# IMU.net
KiCad netlist of a schematic drawn in Altium Designer
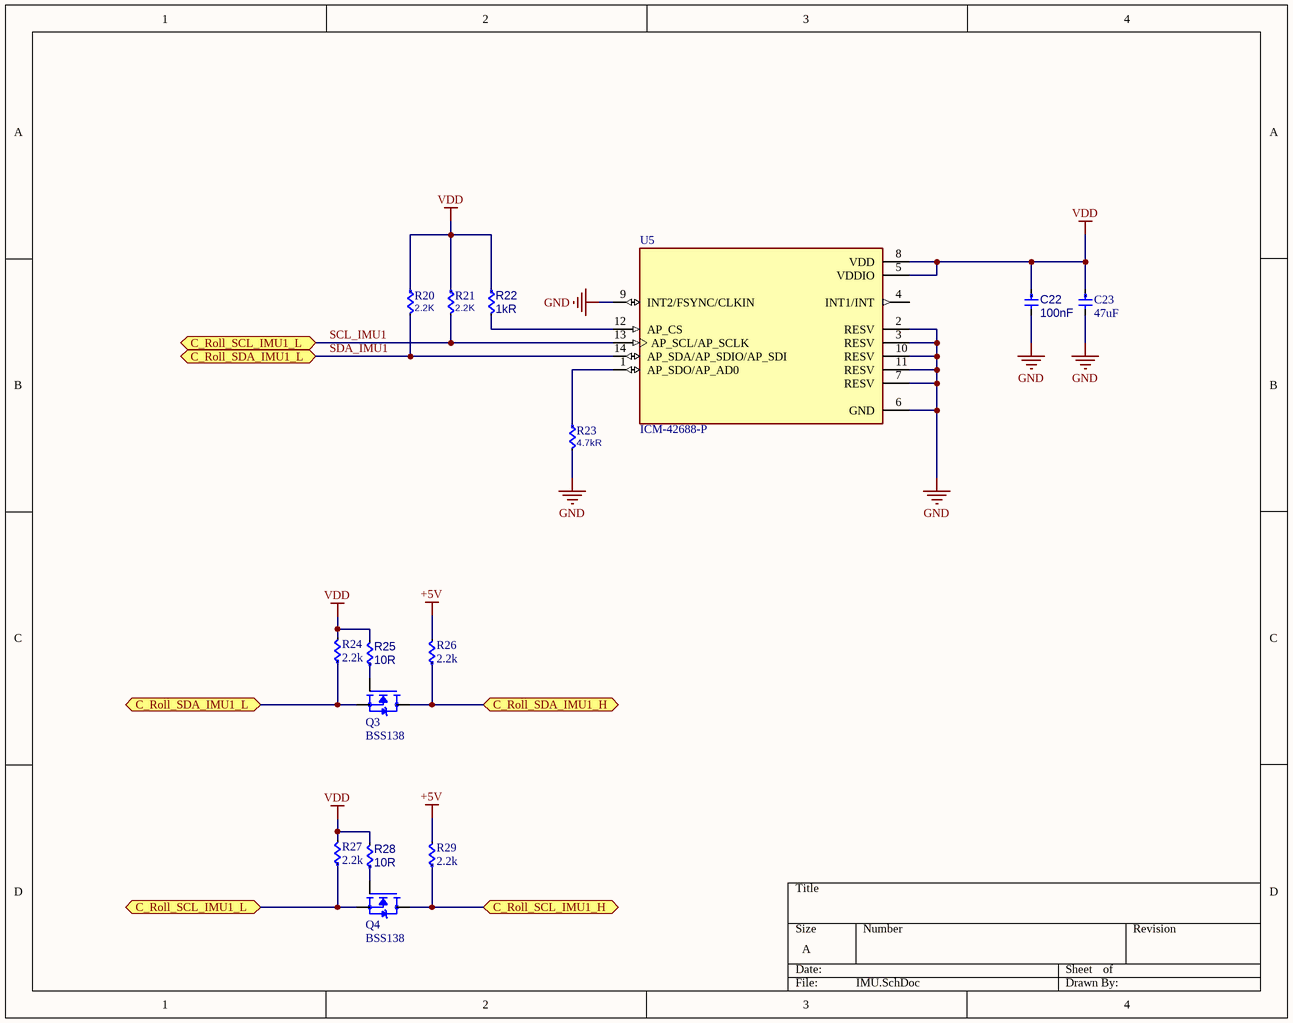
[diagram p0: IMU.SchDoc]

(export (version "E")
  (design (tool "Eeschema 10.0.6"))
  (components
    (comp (ref "C22")
      (value "C0603C104M5RACTU")
      (footprint "CAP0603")
      (description "CAP CER 0.1UF 50V X7R 0603")
      (fields (field (name "TOLERANCE") "20%") (field (name "CAPACITANCE") "100nF"))
      (libsource (lib "rtr") (part "CMP-00691-1"))
    )
    (comp (ref "C23")
      (value "CL21A476MQYNNNE")
      (footprint "CAP0805")
      (description "CAP CER 47UF 6.3V X5R 0805")
      (fields (field (name "TOLERANCE") "20%") (field (name "CAPACITANCE") "47uF"))
      (libsource (lib "rtr") (part "885012107014"))
    )
    (comp (ref "Q3")
      (value "BSS138")
      (footprint "BSS138")
      (description "N-Channel 50 V 220mA (Ta) 350mW (Ta) Surface Mount SOT-23-3")
      (fields (field (name "MF") "onsemi"))
      (libsource (lib "Sbus to Uart") (part "BSS138"))
    )
    (comp (ref "Q4")
      (value "BSS138")
      (footprint "BSS138")
      (description "N-Channel 50 V 220mA (Ta) 350mW (Ta) Surface Mount SOT-23-3")
      (fields (field (name "MF") "onsemi"))
      (libsource (lib "Sbus to Uart") (part "BSS138"))
    )
    (comp (ref "R20")
      (value "RC0603FR-072K2L")
      (footprint "RES0603")
      (description "RES SMD 2.2K OHM 1% 1/10W 0603")
      (fields (field (name "TOLERANCE") "5%") (field (name "RESISTANCE") "2.2K"))
      (libsource (lib "rtr") (part "CMP-01404-1"))
    )
    (comp (ref "R21")
      (value "RC0603FR-072K2L")
      (footprint "RES0603")
      (description "RES SMD 2.2K OHM 1% 1/10W 0603")
      (fields (field (name "TOLERANCE") "5%") (field (name "RESISTANCE") "2.2K"))
      (libsource (lib "rtr") (part "CMP-01404-1"))
    )
    (comp (ref "R22")
      (value "RC0603FR-071KL")
      (footprint "RES0603")
      (description "RES SMD 1K OHM 1% 1/10W 0603")
      (fields
        (field (name "MANUFACTURER") "Yageo")
        (field (name "TOLERANCE") "1%")
        (field (name "RESISTANCE") "1kR")
      )
      (libsource (lib "rtr") (part "CMP-00067-1"))
    )
    (comp (ref "R23")
      (value "RC0603JR-074K7L")
      (footprint "RES0603")
      (description "RES SMD 4.7K OHM 5% 1/10W 0603")
      (fields (field (name "TOLERANCE") "5%") (field (name "RESISTANCE") "4.7kR"))
      (libsource (lib "rtr") (part "CMP-01404-1"))
    )
    (comp (ref "R24")
      (value "2.2k")
      (footprint "RES0603")
      (description "Res Thick Film 0603 2.2K Ohm 1% 0.1W(1/10W) +/-100ppm/C Epoxy Pad SMD T/R")
      (fields
        (field (name "MANUFACTURER") "Yageo Group")
        (field (name "MANUFACTURER PART NUMBER") "RC0603FR-072K2L")
      )
      (libsource (lib "Yaw-Ofil") (part "RC0603FR-072K2L"))
    )
    (comp (ref "R25")
      (value "MCR03EZPJ100")
      (footprint "RES0603")
      (description "RES SMD 10 OHM 5% 1/10W 0603")
      (fields (field (name "TOLERANCE") "5%") (field (name "RESISTANCE") "10R"))
      (libsource (lib "JetsonNX_CSI") (part "CMP-01078-4"))
    )
    (comp (ref "R26")
      (value "2.2k")
      (footprint "RES0603")
      (description "Res Thick Film 0603 2.2K Ohm 1% 0.1W(1/10W) +/-100ppm/C Epoxy Pad SMD T/R")
      (fields
        (field (name "MANUFACTURER") "Yageo Group")
        (field (name "MANUFACTURER PART NUMBER") "RC0603FR-072K2L")
      )
      (libsource (lib "Yaw-Ofil") (part "RC0603FR-072K2L"))
    )
    (comp (ref "R27")
      (value "2.2k")
      (footprint "RES0603")
      (description "Res Thick Film 0603 2.2K Ohm 1% 0.1W(1/10W) +/-100ppm/C Epoxy Pad SMD T/R")
      (fields
        (field (name "MANUFACTURER") "Yageo Group")
        (field (name "MANUFACTURER PART NUMBER") "RC0603FR-072K2L")
      )
      (libsource (lib "Yaw-Ofil") (part "RC0603FR-072K2L"))
    )
    (comp (ref "R28")
      (value "MCR03EZPJ100")
      (footprint "RES0603")
      (description "RES SMD 10 OHM 5% 1/10W 0603")
      (fields (field (name "TOLERANCE") "5%") (field (name "RESISTANCE") "10R"))
      (libsource (lib "JetsonNX_CSI") (part "CMP-01078-4"))
    )
    (comp (ref "R29")
      (value "2.2k")
      (footprint "RES0603")
      (description "Res Thick Film 0603 2.2K Ohm 1% 0.1W(1/10W) +/-100ppm/C Epoxy Pad SMD T/R")
      (fields
        (field (name "MANUFACTURER") "Yageo Group")
        (field (name "MANUFACTURER PART NUMBER") "RC0603FR-072K2L")
      )
      (libsource (lib "Yaw-Ofil") (part "RC0603FR-072K2L"))
    )
    (comp (ref "U5")
      (value "ICM-42688-P")
      (footprint "ICM-42688-P")
      (description "Accelerometer, Gyroscope, 6 Axis Sensor Output")
      (libsource (lib "RTR") (part "ICM-42688-P"))
    )
  )
  (nets
    (net (code "1") (name "+5V") (class "Default")
      (node (ref "R26") (pin "2") (pinfunction "2_2") (pintype "passive"))
      (node (ref "R29") (pin "2") (pinfunction "2_2") (pintype "passive"))
    )
    (net (code "2") (name "/C_Roll_SCL_IMU1_H") (class "Default")
      (node (ref "Q4") (pin "3") (pinfunction "D_3") (pintype "passive"))
      (node (ref "R29") (pin "1") (pinfunction "1_1") (pintype "passive"))
    )
    (net (code "3") (name "/C_Roll_SDA_IMU1_H") (class "Default")
      (node (ref "Q3") (pin "3") (pinfunction "D_3") (pintype "passive"))
      (node (ref "R26") (pin "1") (pinfunction "1_1") (pintype "passive"))
    )
    (net (code "4") (name "/SCL_IMU1") (class "Default")
      (node (ref "Q4") (pin "2") (pinfunction "S_2") (pintype "passive"))
      (node (ref "R21") (pin "2") (pinfunction "2_2") (pintype "passive"))
      (node (ref "R27") (pin "1") (pinfunction "1_1") (pintype "passive"))
      (node (ref "U5") (pin "13") (pinfunction "AP_SCL/AP_SCLK_13") (pintype "input"))
    )
    (net (code "5") (name "/SDA_IMU1") (class "Default")
      (node (ref "Q3") (pin "2") (pinfunction "S_2") (pintype "passive"))
      (node (ref "R20") (pin "2") (pinfunction "2_2") (pintype "passive"))
      (node (ref "R24") (pin "1") (pinfunction "1_1") (pintype "passive"))
      (node (ref "U5") (pin "14") (pinfunction "AP_SDA/AP_SDIO/AP_SDI_14") (pintype "bidirectional"))
    )
    (net (code "6") (name "GND") (class "Default")
      (node (ref "C22") (pin "2") (pinfunction "2_2") (pintype "passive"))
      (node (ref "C23") (pin "2") (pinfunction "2_2") (pintype "passive"))
      (node (ref "R23") (pin "2") (pinfunction "2_2") (pintype "passive"))
      (node (ref "U5") (pin "10") (pinfunction "RESV_10") (pintype "passive"))
      (node (ref "U5") (pin "11") (pinfunction "RESV_11") (pintype "passive"))
      (node (ref "U5") (pin "2") (pinfunction "RESV_2") (pintype "passive"))
      (node (ref "U5") (pin "3") (pinfunction "RESV_3") (pintype "passive"))
      (node (ref "U5") (pin "6") (pinfunction "GND_6") (pintype "power_in"))
      (node (ref "U5") (pin "7") (pinfunction "RESV_7") (pintype "passive"))
      (node (ref "U5") (pin "9") (pinfunction "INT2/FSYNC/CLKIN_9") (pintype "bidirectional"))
    )
    (net (code "7") (name "Net-(Q3-G)") (class "Default")
      (node (ref "Q3") (pin "1") (pinfunction "G_1") (pintype "passive"))
      (node (ref "R25") (pin "1") (pinfunction "1_1") (pintype "passive"))
    )
    (net (code "8") (name "Net-(Q4-G)") (class "Default")
      (node (ref "Q4") (pin "1") (pinfunction "G_1") (pintype "passive"))
      (node (ref "R28") (pin "1") (pinfunction "1_1") (pintype "passive"))
    )
    (net (code "9") (name "Net-(U5-AP_CS)") (class "Default")
      (node (ref "R22") (pin "2") (pinfunction "2_2") (pintype "passive"))
      (node (ref "U5") (pin "12") (pinfunction "AP_CS_12") (pintype "input"))
    )
    (net (code "10") (name "Net-(U5-AP_SDO{slash}AP_AD0)") (class "Default")
      (node (ref "R23") (pin "1") (pinfunction "1_1") (pintype "passive"))
      (node (ref "U5") (pin "1") (pinfunction "AP_SDO/AP_AD0_1") (pintype "bidirectional"))
    )
    (net (code "11") (name "VDD") (class "Default")
      (node (ref "C22") (pin "1") (pinfunction "1_1") (pintype "passive"))
      (node (ref "C23") (pin "1") (pinfunction "1_1") (pintype "passive"))
      (node (ref "R20") (pin "1") (pinfunction "1_1") (pintype "passive"))
      (node (ref "R21") (pin "1") (pinfunction "1_1") (pintype "passive"))
      (node (ref "R22") (pin "1") (pinfunction "1_1") (pintype "passive"))
      (node (ref "R24") (pin "2") (pinfunction "2_2") (pintype "passive"))
      (node (ref "R25") (pin "2") (pinfunction "2_2") (pintype "passive"))
      (node (ref "R27") (pin "2") (pinfunction "2_2") (pintype "passive"))
      (node (ref "R28") (pin "2") (pinfunction "2_2") (pintype "passive"))
      (node (ref "U5") (pin "5") (pinfunction "VDDIO_5") (pintype "power_in"))
      (node (ref "U5") (pin "8") (pinfunction "VDD_8") (pintype "power_in"))
    )
    (net (code "12") (name "unconnected-(U5-INT1{slash}INT-Pad4)") (class "Default")
      (node (ref "U5") (pin "4") (pinfunction "INT1/INT_4") (pintype "output"))
    )
  )
)
